# DM1097_Connector_A.net
KiCad netlist of a schematic drawn in Altium Designer
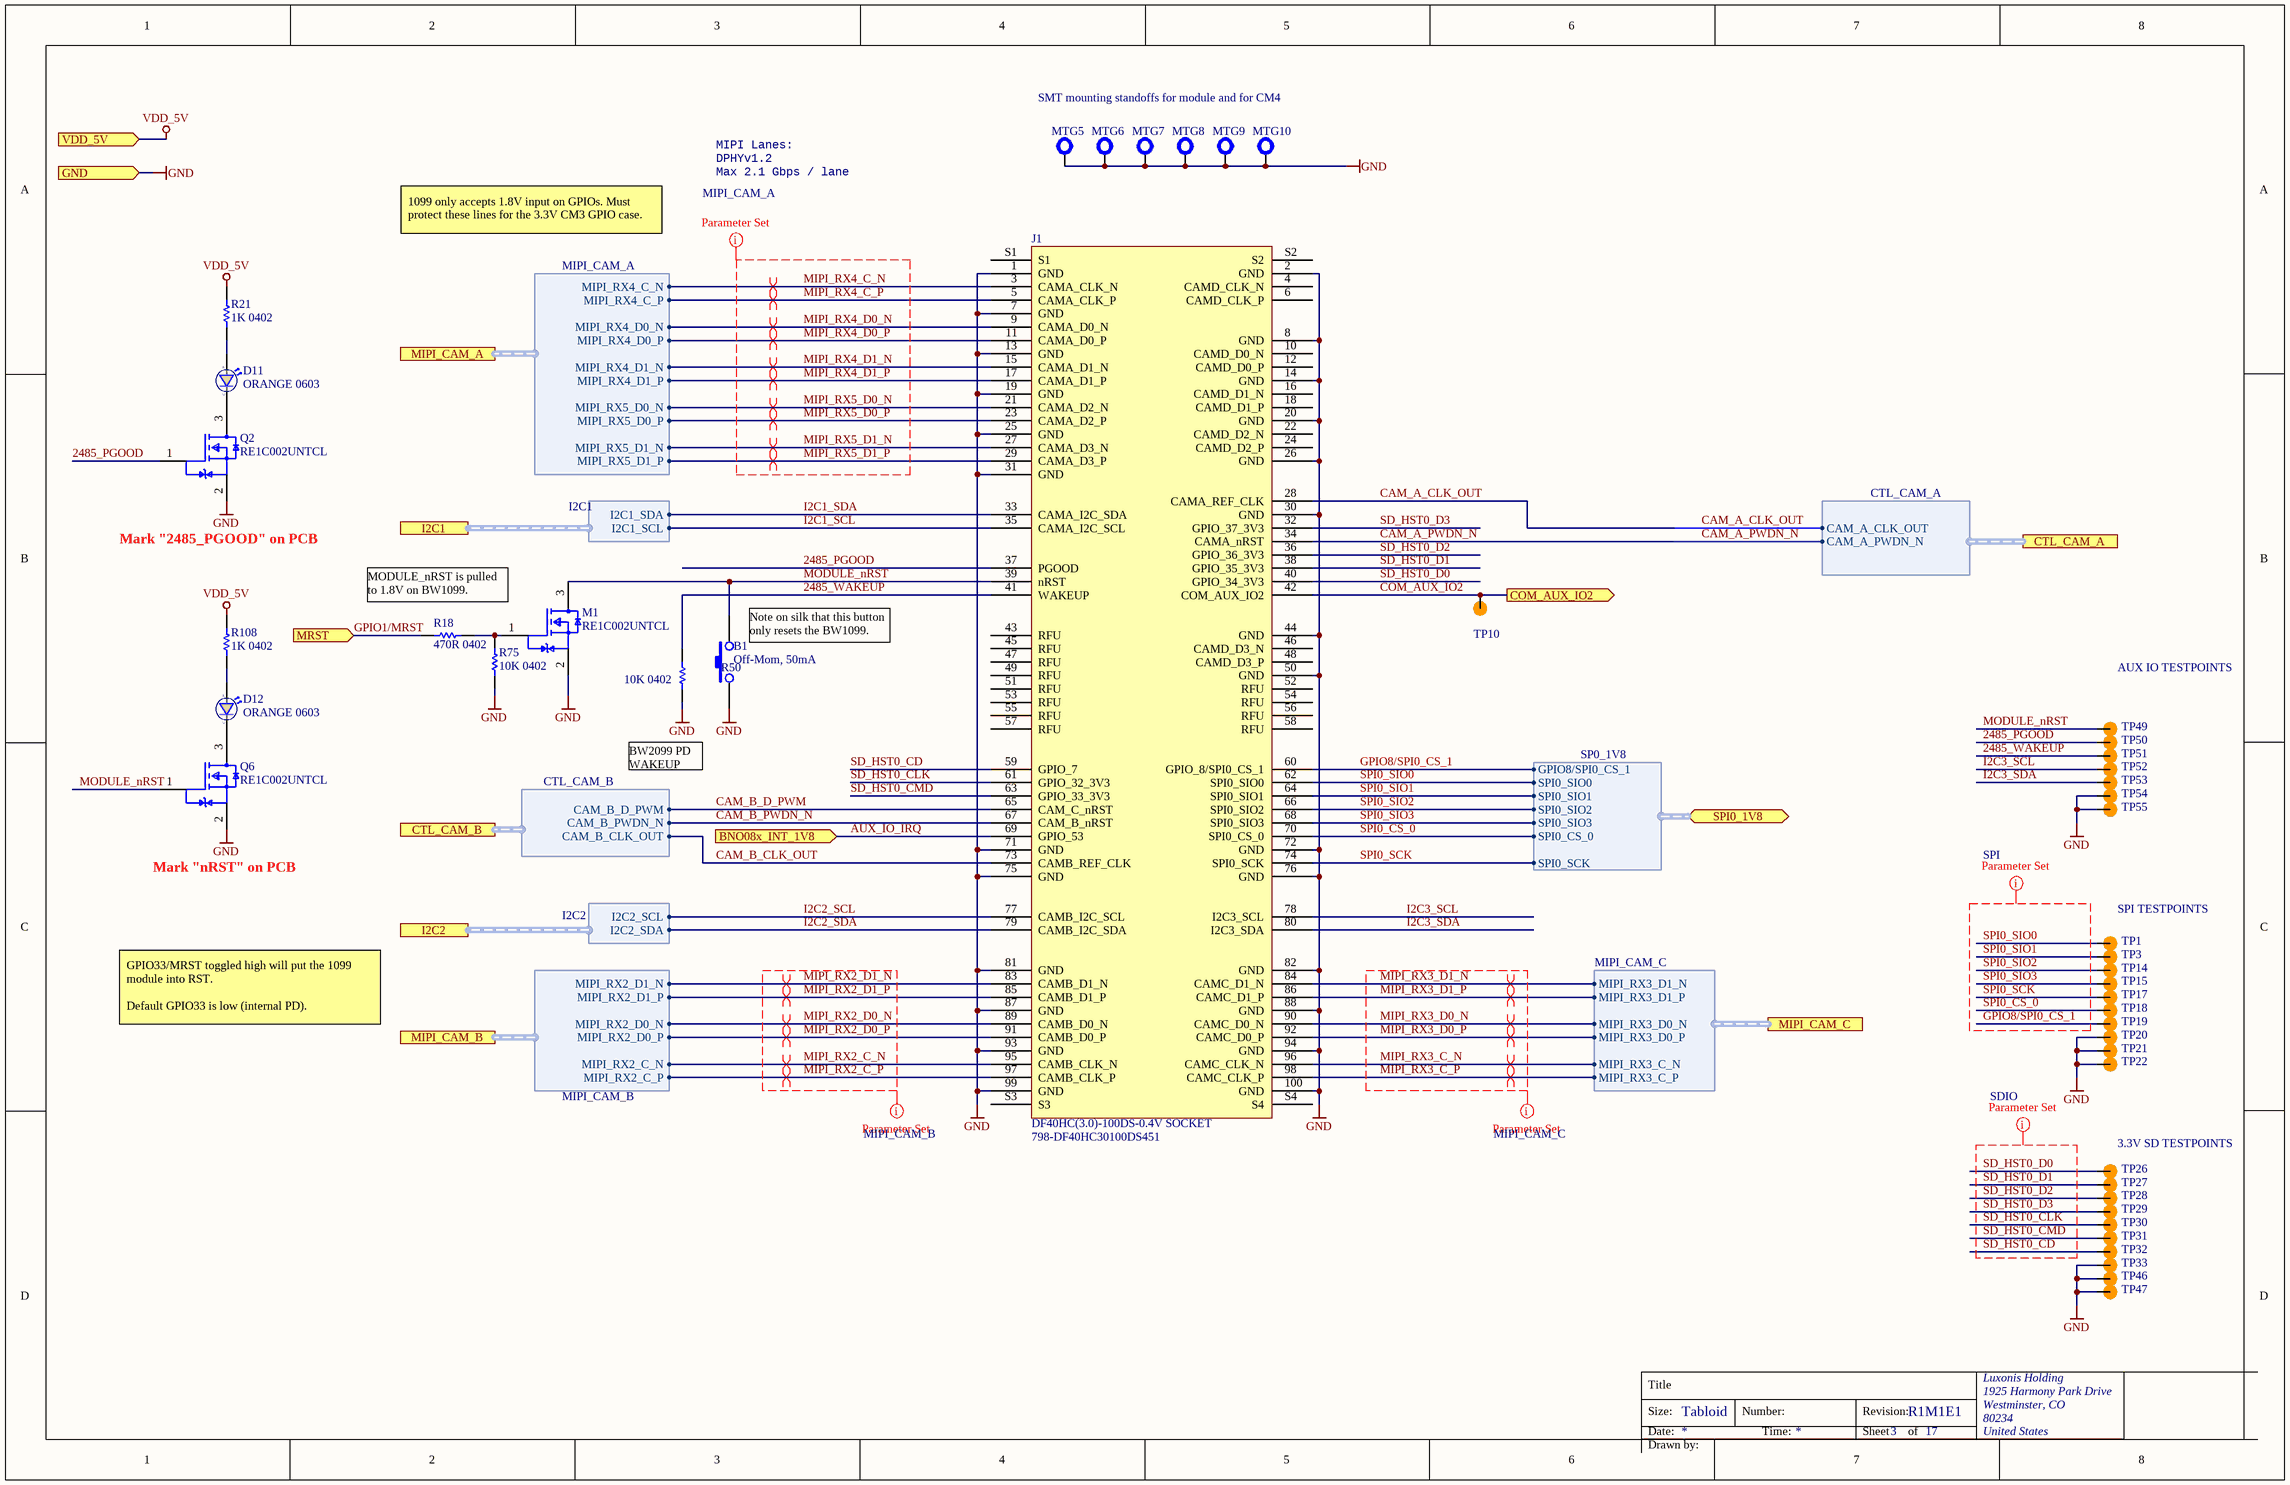
[diagram p0: DM1097_Connector_A.SchDoc]

(export (version "E")
  (design (tool "Eeschema 10.0.6"))
  (components
    (comp (ref "B1")
      (value "Off-Mom, 50mA")
      (footprint "LuxonisMaster:DTSM-32N-V")
      (description "SWITCH TACTILE SMT 3.5mm * 6mm , brown 160gf")
      (libsource (lib "LuxonisMaster") (part "DTSM-32N-V"))
    )
    (comp (ref "D11")
      (value "ORANGE 0603")
      (footprint "LuxonisMaster:SML_D1xx8W")
      (description "LED ORANGE DIFFUSED 0603 SMD Orange 605nm LED Indication - Discrete 2.2V 0603 (1608 Metric)")
      (libsource (lib "LuxonisMaster") (part "SML-D12D8WT86"))
    )
    (comp (ref "D12")
      (value "ORANGE 0603")
      (footprint "LuxonisMaster:SML_D1xx8W")
      (description "LED ORANGE DIFFUSED 0603 SMD Orange 605nm LED Indication - Discrete 2.2V 0603 (1608 Metric)")
      (libsource (lib "LuxonisMaster") (part "SML-D12D8WT86"))
    )
    (comp (ref "J1")
      (value "DF40HC(3.0)-100DS-0.4V SOCKET")
      (footprint "DF40HC-3.0-100DS-0.4V_minpad")
      (description "Conn Board to Board RCP 100 POS 0.4mm Solder ST SMD T/R")
      (fields (field (name "SUPPLIER PART NUMBER 1") "798-DF40HC30100DS451"))
      (libsource (lib "LuxonisMaster_OPAL") (part "BW2099_SCKT_Conn_A"))
    )
    (comp (ref "M1")
      (value "RE1C002UNTCL")
      (footprint "LuxonisMaster:RE1C002UNTCL")
      (description "VISHAY - SI1062X-T1-GE3 - MOSFET Transistor, N Channel, 530 mA, 20 V, 0.35 ohm, 4.5 V, 1 V")
      (libsource (lib "LuxonisMaster") (part "RE1C002UNTCL"))
    )
    (comp (ref "MTG5")
      (value "M2, 3MM steel spacer on M2.5 mounting pad")
      (footprint "9774030943R")
      (description "Spacers/Standoffs")
      (libsource (lib "DM1097_R1M1E1") (part "9774030943R"))
    )
    (comp (ref "MTG6")
      (value "M2, 3MM steel spacer on M2.5 mounting pad")
      (footprint "9774030943R")
      (description "Spacers/Standoffs")
      (libsource (lib "DM1097_R1M1E1") (part "9774030943R"))
    )
    (comp (ref "MTG7")
      (value "M2, 3MM steel spacer on M2.5 mounting pad")
      (footprint "9774030943R")
      (description "Spacers/Standoffs")
      (libsource (lib "DM1097_R1M1E1") (part "9774030943R"))
    )
    (comp (ref "MTG8")
      (value "M2, 3MM steel spacer on M2.5 mounting pad")
      (footprint "9774030943R")
      (description "Spacers/Standoffs")
      (libsource (lib "DM1097_R1M1E1") (part "9774030943R"))
    )
    (comp (ref "MTG9")
      (value "M2, 3MM steel spacer on M2.5 mounting pad")
      (footprint "9774030943R")
      (description "Spacers/Standoffs")
      (libsource (lib "DM1097_R1M1E1") (part "9774030943R"))
    )
    (comp (ref "MTG10")
      (value "M2, 3MM steel spacer on M2.5 mounting pad")
      (footprint "9774030943R")
      (description "Spacers/Standoffs")
      (libsource (lib "DM1097_R1M1E1") (part "9774030943R"))
    )
    (comp (ref "Q2")
      (value "RE1C002UNTCL")
      (footprint "LuxonisMaster:RE1C002UNTCL")
      (description "VISHAY - SI1062X-T1-GE3 - MOSFET Transistor, N Channel, 530 mA, 20 V, 0.35 ohm, 4.5 V, 1 V")
      (libsource (lib "LuxonisMaster") (part "RE1C002UNTCL"))
    )
    (comp (ref "Q6")
      (value "RE1C002UNTCL")
      (footprint "LuxonisMaster:RE1C002UNTCL")
      (description "VISHAY - SI1062X-T1-GE3 - MOSFET Transistor, N Channel, 530 mA, 20 V, 0.35 ohm, 4.5 V, 1 V")
      (libsource (lib "LuxonisMaster") (part "RE1C002UNTCL"))
    )
    (comp (ref "R18")
      (value "470R 0402")
      (footprint "RES_Altium_Vault_Generic:RESC0402(1005)_N")
      (description "RES SMD 470 OHM 1% 1/16W 0402")
      (fields (field (name "TOLERANCE") "1%"))
      (libsource (lib "LuxonisMaster") (part "CRCW0402470RFKED"))
    )
    (comp (ref "R21")
      (value "1K 0402")
      (footprint "RES_Altium_Vault_Generic:RESC0402(1005)_L")
      (fields (field (name "TOLERANCE") "1%"))
      (libsource (lib "LuxonisMaster") (part "RC0402FR-071KL"))
    )
    (comp (ref "R50")
      (value "10K 0402")
      (footprint "RES_Altium_Vault_Generic:RESC0402(1005)_L")
      (fields (field (name "TOLERANCE") "1%"))
      (libsource (lib "LuxonisMaster") (part "RC0402FR-1310KL"))
    )
    (comp (ref "R75")
      (value "10K 0402")
      (footprint "RES_Altium_Vault_Generic:RESC0402(1005)_N")
      (fields (field (name "TOLERANCE") "1%"))
      (libsource (lib "LuxonisMaster") (part "RC0402FR-1310KL"))
    )
    (comp (ref "R108")
      (value "1K 0402")
      (footprint "RES_Altium_Vault_Generic:RESC0402(1005)_L")
      (fields (field (name "TOLERANCE") "1%"))
      (libsource (lib "LuxonisMaster") (part "RC0402FR-071KL"))
    )
    (comp (ref "TP1")
      (value "TP100_200_NS")
      (footprint "LuxonisMaster:TP100_200_NS")
      (libsource (lib "LuxonisMaster") (part "TEST_POINT"))
    )
    (comp (ref "TP3")
      (value "TP100_200_NS")
      (footprint "LuxonisMaster:TP100_200_NS")
      (libsource (lib "LuxonisMaster") (part "TEST_POINT"))
    )
    (comp (ref "TP10")
      (value "TP100_200_NS")
      (footprint "LuxonisMaster:TP100_200_NS")
      (libsource (lib "LuxonisMaster") (part "TEST_POINT"))
    )
    (comp (ref "TP14")
      (value "TP100_200_NS")
      (footprint "LuxonisMaster:TP100_200_NS")
      (libsource (lib "LuxonisMaster") (part "TEST_POINT"))
    )
    (comp (ref "TP15")
      (value "TP100_200_NS")
      (footprint "LuxonisMaster:TP100_200_NS")
      (libsource (lib "LuxonisMaster") (part "TEST_POINT"))
    )
    (comp (ref "TP17")
      (value "TP100_200_NS")
      (footprint "LuxonisMaster:TP100_200_NS")
      (libsource (lib "LuxonisMaster") (part "TEST_POINT"))
    )
    (comp (ref "TP18")
      (value "TP100_200_NS")
      (footprint "LuxonisMaster:TP100_200_NS")
      (libsource (lib "LuxonisMaster") (part "TEST_POINT"))
    )
    (comp (ref "TP19")
      (value "TP100_200_NS")
      (footprint "LuxonisMaster:TP100_200_NS")
      (libsource (lib "LuxonisMaster") (part "TEST_POINT"))
    )
    (comp (ref "TP20")
      (value "TP100_200_NS")
      (footprint "LuxonisMaster:TP100_200_NS")
      (libsource (lib "LuxonisMaster") (part "TEST_POINT"))
    )
    (comp (ref "TP21")
      (value "TP100_200_NS")
      (footprint "LuxonisMaster:TP100_200_NS")
      (libsource (lib "LuxonisMaster") (part "TEST_POINT"))
    )
    (comp (ref "TP22")
      (value "TP100_200_NS")
      (footprint "LuxonisMaster:TP100_200_NS")
      (libsource (lib "LuxonisMaster") (part "TEST_POINT"))
    )
    (comp (ref "TP26")
      (value "TP100_200_NS")
      (footprint "LuxonisMaster:TP100_200_NS")
      (libsource (lib "LuxonisMaster") (part "TEST_POINT"))
    )
    (comp (ref "TP27")
      (value "TP100_200_NS")
      (footprint "LuxonisMaster:TP100_200_NS")
      (libsource (lib "LuxonisMaster") (part "TEST_POINT"))
    )
    (comp (ref "TP28")
      (value "TP100_200_NS")
      (footprint "LuxonisMaster:TP100_200_NS")
      (libsource (lib "LuxonisMaster") (part "TEST_POINT"))
    )
    (comp (ref "TP29")
      (value "TP100_200_NS")
      (footprint "LuxonisMaster:TP100_200_NS")
      (libsource (lib "LuxonisMaster") (part "TEST_POINT"))
    )
    (comp (ref "TP30")
      (value "TP100_200_NS")
      (footprint "LuxonisMaster:TP100_200_NS")
      (libsource (lib "LuxonisMaster") (part "TEST_POINT"))
    )
    (comp (ref "TP31")
      (value "TP100_200_NS")
      (footprint "LuxonisMaster:TP100_200_NS")
      (libsource (lib "LuxonisMaster") (part "TEST_POINT"))
    )
    (comp (ref "TP32")
      (value "TP100_200_NS")
      (footprint "LuxonisMaster:TP100_200_NS")
      (libsource (lib "LuxonisMaster") (part "TEST_POINT"))
    )
    (comp (ref "TP33")
      (value "TP100_200_NS")
      (footprint "LuxonisMaster:TP100_200_NS")
      (libsource (lib "LuxonisMaster") (part "TEST_POINT"))
    )
    (comp (ref "TP46")
      (value "TP100_200_NS")
      (footprint "LuxonisMaster:TP100_200_NS")
      (libsource (lib "LuxonisMaster") (part "TEST_POINT"))
    )
    (comp (ref "TP47")
      (value "TP100_200_NS")
      (footprint "LuxonisMaster:TP100_200_NS")
      (libsource (lib "LuxonisMaster") (part "TEST_POINT"))
    )
    (comp (ref "TP49")
      (value "TP100_200_NS")
      (footprint "LuxonisMaster:TP100_200_NS")
      (libsource (lib "LuxonisMaster") (part "TEST_POINT"))
    )
    (comp (ref "TP50")
      (value "TP100_200_NS")
      (footprint "LuxonisMaster:TP100_200_NS")
      (libsource (lib "LuxonisMaster") (part "TEST_POINT"))
    )
    (comp (ref "TP51")
      (value "TP100_200_NS")
      (footprint "LuxonisMaster:TP100_200_NS")
      (libsource (lib "LuxonisMaster") (part "TEST_POINT"))
    )
    (comp (ref "TP52")
      (value "TP100_200_NS")
      (footprint "LuxonisMaster:TP100_200_NS")
      (libsource (lib "LuxonisMaster") (part "TEST_POINT"))
    )
    (comp (ref "TP53")
      (value "TP100_200_NS")
      (footprint "LuxonisMaster:TP100_200_NS")
      (libsource (lib "LuxonisMaster") (part "TEST_POINT"))
    )
    (comp (ref "TP54")
      (value "TP100_200_NS")
      (footprint "LuxonisMaster:TP100_200_NS")
      (libsource (lib "LuxonisMaster") (part "TEST_POINT"))
    )
    (comp (ref "TP55")
      (value "TP100_200_NS")
      (footprint "LuxonisMaster:TP100_200_NS")
      (libsource (lib "LuxonisMaster") (part "TEST_POINT"))
    )
  )
  (nets
    (net (code "9") (name "/2485_PGOOD") (class "Default")
      (node (ref "J1") (pin "37") (pinfunction "PGOOD_37") (pintype "passive"))
      (node (ref "Q2") (pin "1") (pinfunction "Gate_1") (pintype "passive"))
      (node (ref "TP50") (pin "1") (pintype "passive"))
    )
    (net (code "10") (name "/2485_WAKEUP") (class "Default")
      (node (ref "J1") (pin "41") (pinfunction "WAKEUP_41") (pintype "passive"))
      (node (ref "R50") (pin "2") (pinfunction "2_2") (pintype "passive"))
      (node (ref "TP51") (pin "1") (pintype "passive"))
    )
    (net (code "11") (name "/AUX_IO_IRQ") (class "Default")
      (node (ref "J1") (pin "69") (pinfunction "GPIO_53_69") (pintype "passive"))
    )
    (net (code "12") (name "/CAM_A_CLK_OUT") (class "Default")
      (node (ref "J1") (pin "28") (pinfunction "CAMA_REF_CLK_28") (pintype "passive"))
    )
    (net (code "13") (name "/CAM_A_PWDN_N") (class "Default")
      (node (ref "J1") (pin "34") (pinfunction "CAMA_nRST_34") (pintype "passive"))
    )
    (net (code "14") (name "/CAM_B_CLK_OUT") (class "Default")
      (node (ref "J1") (pin "73") (pinfunction "CAMB_REF_CLK_73") (pintype "passive"))
    )
    (net (code "15") (name "/CAM_B_D_PWM") (class "Default")
      (node (ref "J1") (pin "65") (pinfunction "CAM_C_nRST_65") (pintype "passive"))
    )
    (net (code "16") (name "/CAM_B_PWDN_N") (class "Default")
      (node (ref "J1") (pin "67") (pinfunction "CAM_B_nRST_67") (pintype "passive"))
    )
    (net (code "17") (name "/COM_AUX_IO2") (class "Default")
      (node (ref "J1") (pin "42") (pinfunction "COM_AUX_IO2_42") (pintype "passive"))
      (node (ref "TP10") (pin "1") (pintype "passive"))
    )
    (net (code "18") (name "/GPIO1{slash}MRST") (class "Default")
      (node (ref "R18") (pin "1") (pinfunction "1_1") (pintype "passive"))
    )
    (net (code "19") (name "/GPIO8{slash}SPI0_CS_1") (class "Default")
      (node (ref "J1") (pin "60") (pinfunction "GPIO_8/SPI0_CS_1_60") (pintype "passive"))
      (node (ref "TP19") (pin "1") (pintype "passive"))
    )
    (net (code "20") (name "/I2C1_SCL") (class "Default")
      (node (ref "J1") (pin "35") (pinfunction "CAMA_I2C_SCL_35") (pintype "passive"))
    )
    (net (code "21") (name "/I2C1_SDA") (class "Default")
      (node (ref "J1") (pin "33") (pinfunction "CAMA_I2C_SDA_33") (pintype "passive"))
    )
    (net (code "22") (name "/I2C2_SCL") (class "Default")
      (node (ref "J1") (pin "77") (pinfunction "CAMB_I2C_SCL_77") (pintype "passive"))
    )
    (net (code "23") (name "/I2C2_SDA") (class "Default")
      (node (ref "J1") (pin "79") (pinfunction "CAMB_I2C_SDA_79") (pintype "passive"))
    )
    (net (code "24") (name "/I2C3_SCL") (class "Default")
      (node (ref "J1") (pin "78") (pinfunction "I2C3_SCL_78") (pintype "passive"))
      (node (ref "TP52") (pin "1") (pintype "passive"))
    )
    (net (code "25") (name "/I2C3_SDA") (class "Default")
      (node (ref "J1") (pin "80") (pinfunction "I2C3_SDA_80") (pintype "passive"))
      (node (ref "TP53") (pin "1") (pintype "passive"))
    )
    (net (code "26") (name "/MIPI_RX2_C_N") (class "Default")
      (node (ref "J1") (pin "95") (pinfunction "CAMB_CLK_N_95") (pintype "passive"))
    )
    (net (code "27") (name "/MIPI_RX2_C_P") (class "Default")
      (node (ref "J1") (pin "97") (pinfunction "CAMB_CLK_P_97") (pintype "passive"))
    )
    (net (code "28") (name "/MIPI_RX2_D0_N") (class "Default")
      (node (ref "J1") (pin "89") (pinfunction "CAMB_D0_N_89") (pintype "passive"))
    )
    (net (code "29") (name "/MIPI_RX2_D0_P") (class "Default")
      (node (ref "J1") (pin "91") (pinfunction "CAMB_D0_P_91") (pintype "passive"))
    )
    (net (code "30") (name "/MIPI_RX2_D1_N") (class "Default")
      (node (ref "J1") (pin "83") (pinfunction "CAMB_D1_N_83") (pintype "passive"))
    )
    (net (code "31") (name "/MIPI_RX2_D1_P") (class "Default")
      (node (ref "J1") (pin "85") (pinfunction "CAMB_D1_P_85") (pintype "passive"))
    )
    (net (code "32") (name "/MIPI_RX3_C_N") (class "Default")
      (node (ref "J1") (pin "96") (pinfunction "CAMC_CLK_N_96") (pintype "passive"))
    )
    (net (code "33") (name "/MIPI_RX3_C_P") (class "Default")
      (node (ref "J1") (pin "98") (pinfunction "CAMC_CLK_P_98") (pintype "passive"))
    )
    (net (code "34") (name "/MIPI_RX3_D0_N") (class "Default")
      (node (ref "J1") (pin "90") (pinfunction "CAMC_D0_N_90") (pintype "passive"))
    )
    (net (code "35") (name "/MIPI_RX3_D0_P") (class "Default")
      (node (ref "J1") (pin "92") (pinfunction "CAMC_D0_P_92") (pintype "passive"))
    )
    (net (code "36") (name "/MIPI_RX3_D1_N") (class "Default")
      (node (ref "J1") (pin "84") (pinfunction "CAMC_D1_N_84") (pintype "passive"))
    )
    (net (code "37") (name "/MIPI_RX3_D1_P") (class "Default")
      (node (ref "J1") (pin "86") (pinfunction "CAMC_D1_P_86") (pintype "passive"))
    )
    (net (code "38") (name "/MIPI_RX4_C_N") (class "Default")
      (node (ref "J1") (pin "3") (pinfunction "CAMA_CLK_N_3") (pintype "passive"))
    )
    (net (code "39") (name "/MIPI_RX4_C_P") (class "Default")
      (node (ref "J1") (pin "5") (pinfunction "CAMA_CLK_P_5") (pintype "passive"))
    )
    (net (code "40") (name "/MIPI_RX4_D0_N") (class "Default")
      (node (ref "J1") (pin "9") (pinfunction "CAMA_D0_N_9") (pintype "passive"))
    )
    (net (code "41") (name "/MIPI_RX4_D0_P") (class "Default")
      (node (ref "J1") (pin "11") (pinfunction "CAMA_D0_P_11") (pintype "passive"))
    )
    (net (code "42") (name "/MIPI_RX4_D1_N") (class "Default")
      (node (ref "J1") (pin "15") (pinfunction "CAMA_D1_N_15") (pintype "passive"))
    )
    (net (code "43") (name "/MIPI_RX4_D1_P") (class "Default")
      (node (ref "J1") (pin "17") (pinfunction "CAMA_D1_P_17") (pintype "passive"))
    )
    (net (code "44") (name "/MIPI_RX5_D0_N") (class "Default")
      (node (ref "J1") (pin "21") (pinfunction "CAMA_D2_N_21") (pintype "passive"))
    )
    (net (code "45") (name "/MIPI_RX5_D0_P") (class "Default")
      (node (ref "J1") (pin "23") (pinfunction "CAMA_D2_P_23") (pintype "passive"))
    )
    (net (code "46") (name "/MIPI_RX5_D1_N") (class "Default")
      (node (ref "J1") (pin "27") (pinfunction "CAMA_D3_N_27") (pintype "passive"))
    )
    (net (code "47") (name "/MIPI_RX5_D1_P") (class "Default")
      (node (ref "J1") (pin "29") (pinfunction "CAMA_D3_P_29") (pintype "passive"))
    )
    (net (code "48") (name "/MODULE_nRST") (class "Default")
      (node (ref "B1") (pin "2") (pinfunction "2_2") (pintype "passive"))
      (node (ref "J1") (pin "39") (pinfunction "nRST_39") (pintype "passive"))
      (node (ref "M1") (pin "3") (pinfunction "Drain_3") (pintype "passive"))
      (node (ref "Q6") (pin "1") (pinfunction "Gate_1") (pintype "passive"))
      (node (ref "TP49") (pin "1") (pintype "passive"))
    )
    (net (code "49") (name "/SD_HST0_CD") (class "Default")
      (node (ref "J1") (pin "59") (pinfunction "GPIO_7_59") (pintype "passive"))
      (node (ref "TP32") (pin "1") (pintype "passive"))
    )
    (net (code "50") (name "/SD_HST0_CLK") (class "Default")
      (node (ref "J1") (pin "61") (pinfunction "GPIO_32_3V3_61") (pintype "passive"))
      (node (ref "TP30") (pin "1") (pintype "passive"))
    )
    (net (code "51") (name "/SD_HST0_CMD") (class "Default")
      (node (ref "J1") (pin "63") (pinfunction "GPIO_33_3V3_63") (pintype "passive"))
      (node (ref "TP31") (pin "1") (pintype "passive"))
    )
    (net (code "52") (name "/SD_HST0_D0") (class "Default")
      (node (ref "J1") (pin "40") (pinfunction "GPIO_34_3V3_40") (pintype "passive"))
      (node (ref "TP26") (pin "1") (pintype "passive"))
    )
    (net (code "53") (name "/SD_HST0_D1") (class "Default")
      (node (ref "J1") (pin "38") (pinfunction "GPIO_35_3V3_38") (pintype "passive"))
      (node (ref "TP27") (pin "1") (pintype "passive"))
    )
    (net (code "54") (name "/SD_HST0_D2") (class "Default")
      (node (ref "J1") (pin "36") (pinfunction "GPIO_36_3V3_36") (pintype "passive"))
      (node (ref "TP28") (pin "1") (pintype "passive"))
    )
    (net (code "55") (name "/SD_HST0_D3") (class "Default")
      (node (ref "J1") (pin "32") (pinfunction "GPIO_37_3V3_32") (pintype "passive"))
      (node (ref "TP29") (pin "1") (pintype "passive"))
    )
    (net (code "56") (name "/SPI0_CS_0") (class "Default")
      (node (ref "J1") (pin "70") (pinfunction "SPI0_CS_0_70") (pintype "passive"))
      (node (ref "TP18") (pin "1") (pintype "passive"))
    )
    (net (code "57") (name "/SPI0_SCK") (class "Default")
      (node (ref "J1") (pin "74") (pinfunction "SPI0_SCK_74") (pintype "passive"))
      (node (ref "TP17") (pin "1") (pintype "passive"))
    )
    (net (code "58") (name "/SPI0_SIO0") (class "Default")
      (node (ref "J1") (pin "62") (pinfunction "SPI0_SIO0_62") (pintype "passive"))
      (node (ref "TP1") (pin "1") (pintype "passive"))
    )
    (net (code "59") (name "/SPI0_SIO1") (class "Default")
      (node (ref "J1") (pin "64") (pinfunction "SPI0_SIO1_64") (pintype "passive"))
      (node (ref "TP3") (pin "1") (pintype "passive"))
    )
    (net (code "60") (name "/SPI0_SIO2") (class "Default")
      (node (ref "J1") (pin "66") (pinfunction "SPI0_SIO2_66") (pintype "passive"))
      (node (ref "TP14") (pin "1") (pintype "passive"))
    )
    (net (code "61") (name "/SPI0_SIO3") (class "Default")
      (node (ref "J1") (pin "68") (pinfunction "SPI0_SIO3_68") (pintype "passive"))
      (node (ref "TP15") (pin "1") (pintype "passive"))
    )
    (net (code "70") (name "GND") (class "Default")
      (node (ref "B1") (pin "1") (pinfunction "1_1") (pintype "passive"))
      (node (ref "J1") (pin "1") (pinfunction "GND_1") (pintype "passive"))
      (node (ref "J1") (pin "100") (pinfunction "GND_100") (pintype "passive"))
      (node (ref "J1") (pin "13") (pinfunction "GND_13") (pintype "passive"))
      (node (ref "J1") (pin "14") (pinfunction "GND_14") (pintype "passive"))
      (node (ref "J1") (pin "19") (pinfunction "GND_19") (pintype "passive"))
      (node (ref "J1") (pin "2") (pinfunction "GND_2") (pintype "passive"))
      (node (ref "J1") (pin "20") (pinfunction "GND_20") (pintype "passive"))
      (node (ref "J1") (pin "25") (pinfunction "GND_25") (pintype "passive"))
      (node (ref "J1") (pin "26") (pinfunction "GND_26") (pintype "passive"))
      (node (ref "J1") (pin "30") (pinfunction "GND_30") (pintype "passive"))
      (node (ref "J1") (pin "31") (pinfunction "GND_31") (pintype "passive"))
      (node (ref "J1") (pin "44") (pinfunction "GND_44") (pintype "passive"))
      (node (ref "J1") (pin "50") (pinfunction "GND_50") (pintype "passive"))
      (node (ref "J1") (pin "7") (pinfunction "GND_7") (pintype "passive"))
      (node (ref "J1") (pin "71") (pinfunction "GND_71") (pintype "passive"))
      (node (ref "J1") (pin "72") (pinfunction "GND_72") (pintype "passive"))
      (node (ref "J1") (pin "75") (pinfunction "GND_75") (pintype "passive"))
      (node (ref "J1") (pin "76") (pinfunction "GND_76") (pintype "passive"))
      (node (ref "J1") (pin "8") (pinfunction "GND_8") (pintype "passive"))
      (node (ref "J1") (pin "81") (pinfunction "GND_81") (pintype "passive"))
      (node (ref "J1") (pin "82") (pinfunction "GND_82") (pintype "passive"))
      (node (ref "J1") (pin "87") (pinfunction "GND_87") (pintype "passive"))
      (node (ref "J1") (pin "88") (pinfunction "GND_88") (pintype "passive"))
      (node (ref "J1") (pin "93") (pinfunction "GND_93") (pintype "passive"))
      (node (ref "J1") (pin "94") (pinfunction "GND_94") (pintype "passive"))
      (node (ref "J1") (pin "99") (pinfunction "GND_99") (pintype "passive"))
      (node (ref "M1") (pin "2") (pinfunction "Source_2") (pintype "passive"))
      (node (ref "MTG10") (pin "1") (pintype "passive"))
      (node (ref "MTG5") (pin "1") (pintype "passive"))
      (node (ref "MTG6") (pin "1") (pintype "passive"))
      (node (ref "MTG7") (pin "1") (pintype "passive"))
      (node (ref "MTG8") (pin "1") (pintype "passive"))
      (node (ref "MTG9") (pin "1") (pintype "passive"))
      (node (ref "Q2") (pin "2") (pinfunction "Source_2") (pintype "passive"))
      (node (ref "Q6") (pin "2") (pinfunction "Source_2") (pintype "passive"))
      (node (ref "R50") (pin "1") (pinfunction "1_1") (pintype "passive"))
      (node (ref "R75") (pin "1") (pinfunction "1_1") (pintype "passive"))
      (node (ref "TP20") (pin "1") (pintype "passive"))
      (node (ref "TP21") (pin "1") (pintype "passive"))
      (node (ref "TP22") (pin "1") (pintype "passive"))
      (node (ref "TP33") (pin "1") (pintype "passive"))
      (node (ref "TP46") (pin "1") (pintype "passive"))
      (node (ref "TP47") (pin "1") (pintype "passive"))
      (node (ref "TP54") (pin "1") (pintype "passive"))
      (node (ref "TP55") (pin "1") (pintype "passive"))
    )
    (net (code "71") (name "Net-(D11-A)") (class "Default")
      (node (ref "D11") (pin "2") (pinfunction "A_2") (pintype "passive"))
      (node (ref "R21") (pin "1") (pinfunction "1_1") (pintype "passive"))
    )
    (net (code "72") (name "Net-(D11-C)") (class "Default")
      (node (ref "D11") (pin "1") (pinfunction "C_1") (pintype "passive"))
      (node (ref "Q2") (pin "3") (pinfunction "Drain_3") (pintype "passive"))
    )
    (net (code "73") (name "Net-(D12-A)") (class "Default")
      (node (ref "D12") (pin "2") (pinfunction "A_2") (pintype "passive"))
      (node (ref "R108") (pin "1") (pinfunction "1_1") (pintype "passive"))
    )
    (net (code "74") (name "Net-(D12-C)") (class "Default")
      (node (ref "D12") (pin "1") (pinfunction "C_1") (pintype "passive"))
      (node (ref "Q6") (pin "3") (pinfunction "Drain_3") (pintype "passive"))
    )
    (net (code "75") (name "Net-(M1-Gate)") (class "Default")
      (node (ref "M1") (pin "1") (pinfunction "Gate_1") (pintype "passive"))
      (node (ref "R18") (pin "2") (pinfunction "2_2") (pintype "passive"))
      (node (ref "R75") (pin "2") (pinfunction "2_2") (pintype "passive"))
    )
    (net (code "76") (name "VDD_5V") (class "Default")
      (node (ref "R108") (pin "2") (pinfunction "2_2") (pintype "passive"))
      (node (ref "R21") (pin "2") (pinfunction "2_2") (pintype "passive"))
    )
    (net (code "77") (name "unconnected-(J1-CAMD_CLK_N-Pad4)") (class "Default")
      (node (ref "J1") (pin "4") (pinfunction "CAMD_CLK_N_4") (pintype "passive"))
    )
    (net (code "78") (name "unconnected-(J1-CAMD_CLK_P-Pad6)") (class "Default")
      (node (ref "J1") (pin "6") (pinfunction "CAMD_CLK_P_6") (pintype "passive"))
    )
    (net (code "79") (name "unconnected-(J1-CAMD_D0_N-Pad10)") (class "Default")
      (node (ref "J1") (pin "10") (pinfunction "CAMD_D0_N_10") (pintype "passive"))
    )
    (net (code "80") (name "unconnected-(J1-CAMD_D0_P-Pad12)") (class "Default")
      (node (ref "J1") (pin "12") (pinfunction "CAMD_D0_P_12") (pintype "passive"))
    )
    (net (code "81") (name "unconnected-(J1-CAMD_D1_N-Pad16)") (class "Default")
      (node (ref "J1") (pin "16") (pinfunction "CAMD_D1_N_16") (pintype "passive"))
    )
    (net (code "82") (name "unconnected-(J1-CAMD_D1_P-Pad18)") (class "Default")
      (node (ref "J1") (pin "18") (pinfunction "CAMD_D1_P_18") (pintype "passive"))
    )
    (net (code "83") (name "unconnected-(J1-CAMD_D2_N-Pad22)") (class "Default")
      (node (ref "J1") (pin "22") (pinfunction "CAMD_D2_N_22") (pintype "passive"))
    )
    (net (code "84") (name "unconnected-(J1-CAMD_D2_P-Pad24)") (class "Default")
      (node (ref "J1") (pin "24") (pinfunction "CAMD_D2_P_24") (pintype "passive"))
    )
    (net (code "85") (name "unconnected-(J1-CAMD_D3_N-Pad46)") (class "Default")
      (node (ref "J1") (pin "46") (pinfunction "CAMD_D3_N_46") (pintype "passive"))
    )
    (net (code "86") (name "unconnected-(J1-CAMD_D3_P-Pad48)") (class "Default")
      (node (ref "J1") (pin "48") (pinfunction "CAMD_D3_P_48") (pintype "passive"))
    )
    (net (code "87") (name "unconnected-(J1-PadS1)") (class "Default")
      (node (ref "J1") (pin "S1") (pinfunction "S1_S1") (pintype "passive"))
    )
    (net (code "88") (name "unconnected-(J1-PadS2)") (class "Default")
      (node (ref "J1") (pin "S2") (pinfunction "S2_S2") (pintype "passive"))
    )
    (net (code "89") (name "unconnected-(J1-PadS3)") (class "Default")
      (node (ref "J1") (pin "S3") (pinfunction "S3_S3") (pintype "passive"))
    )
    (net (code "90") (name "unconnected-(J1-PadS4)") (class "Default")
      (node (ref "J1") (pin "S4") (pinfunction "S4_S4") (pintype "passive"))
    )
    (net (code "91") (name "unconnected-(J1-RFU-Pad43)") (class "Default")
      (node (ref "J1") (pin "43") (pinfunction "RFU_43") (pintype "passive"))
    )
    (net (code "92") (name "unconnected-(J1-RFU-Pad45)") (class "Default")
      (node (ref "J1") (pin "45") (pinfunction "RFU_45") (pintype "passive"))
    )
    (net (code "93") (name "unconnected-(J1-RFU-Pad47)") (class "Default")
      (node (ref "J1") (pin "47") (pinfunction "RFU_47") (pintype "passive"))
    )
    (net (code "94") (name "unconnected-(J1-RFU-Pad49)") (class "Default")
      (node (ref "J1") (pin "49") (pinfunction "RFU_49") (pintype "passive"))
    )
    (net (code "95") (name "unconnected-(J1-RFU-Pad51)") (class "Default")
      (node (ref "J1") (pin "51") (pinfunction "RFU_51") (pintype "passive"))
    )
    (net (code "96") (name "unconnected-(J1-RFU-Pad52)") (class "Default")
      (node (ref "J1") (pin "52") (pinfunction "RFU_52") (pintype "passive"))
    )
    (net (code "97") (name "unconnected-(J1-RFU-Pad53)") (class "Default")
      (node (ref "J1") (pin "53") (pinfunction "RFU_53") (pintype "passive"))
    )
    (net (code "98") (name "unconnected-(J1-RFU-Pad54)") (class "Default")
      (node (ref "J1") (pin "54") (pinfunction "RFU_54") (pintype "passive"))
    )
    (net (code "99") (name "unconnected-(J1-RFU-Pad55)") (class "Default")
      (node (ref "J1") (pin "55") (pinfunction "RFU_55") (pintype "passive"))
    )
    (net (code "100") (name "unconnected-(J1-RFU-Pad56)") (class "Default")
      (node (ref "J1") (pin "56") (pinfunction "RFU_56") (pintype "passive"))
    )
    (net (code "101") (name "unconnected-(J1-RFU-Pad57)") (class "Default")
      (node (ref "J1") (pin "57") (pinfunction "RFU_57") (pintype "passive"))
    )
    (net (code "102") (name "unconnected-(J1-RFU-Pad58)") (class "Default")
      (node (ref "J1") (pin "58") (pinfunction "RFU_58") (pintype "passive"))
    )
  )
)
